# Main.net
KiCad netlist of a schematic drawn in Altium Designer
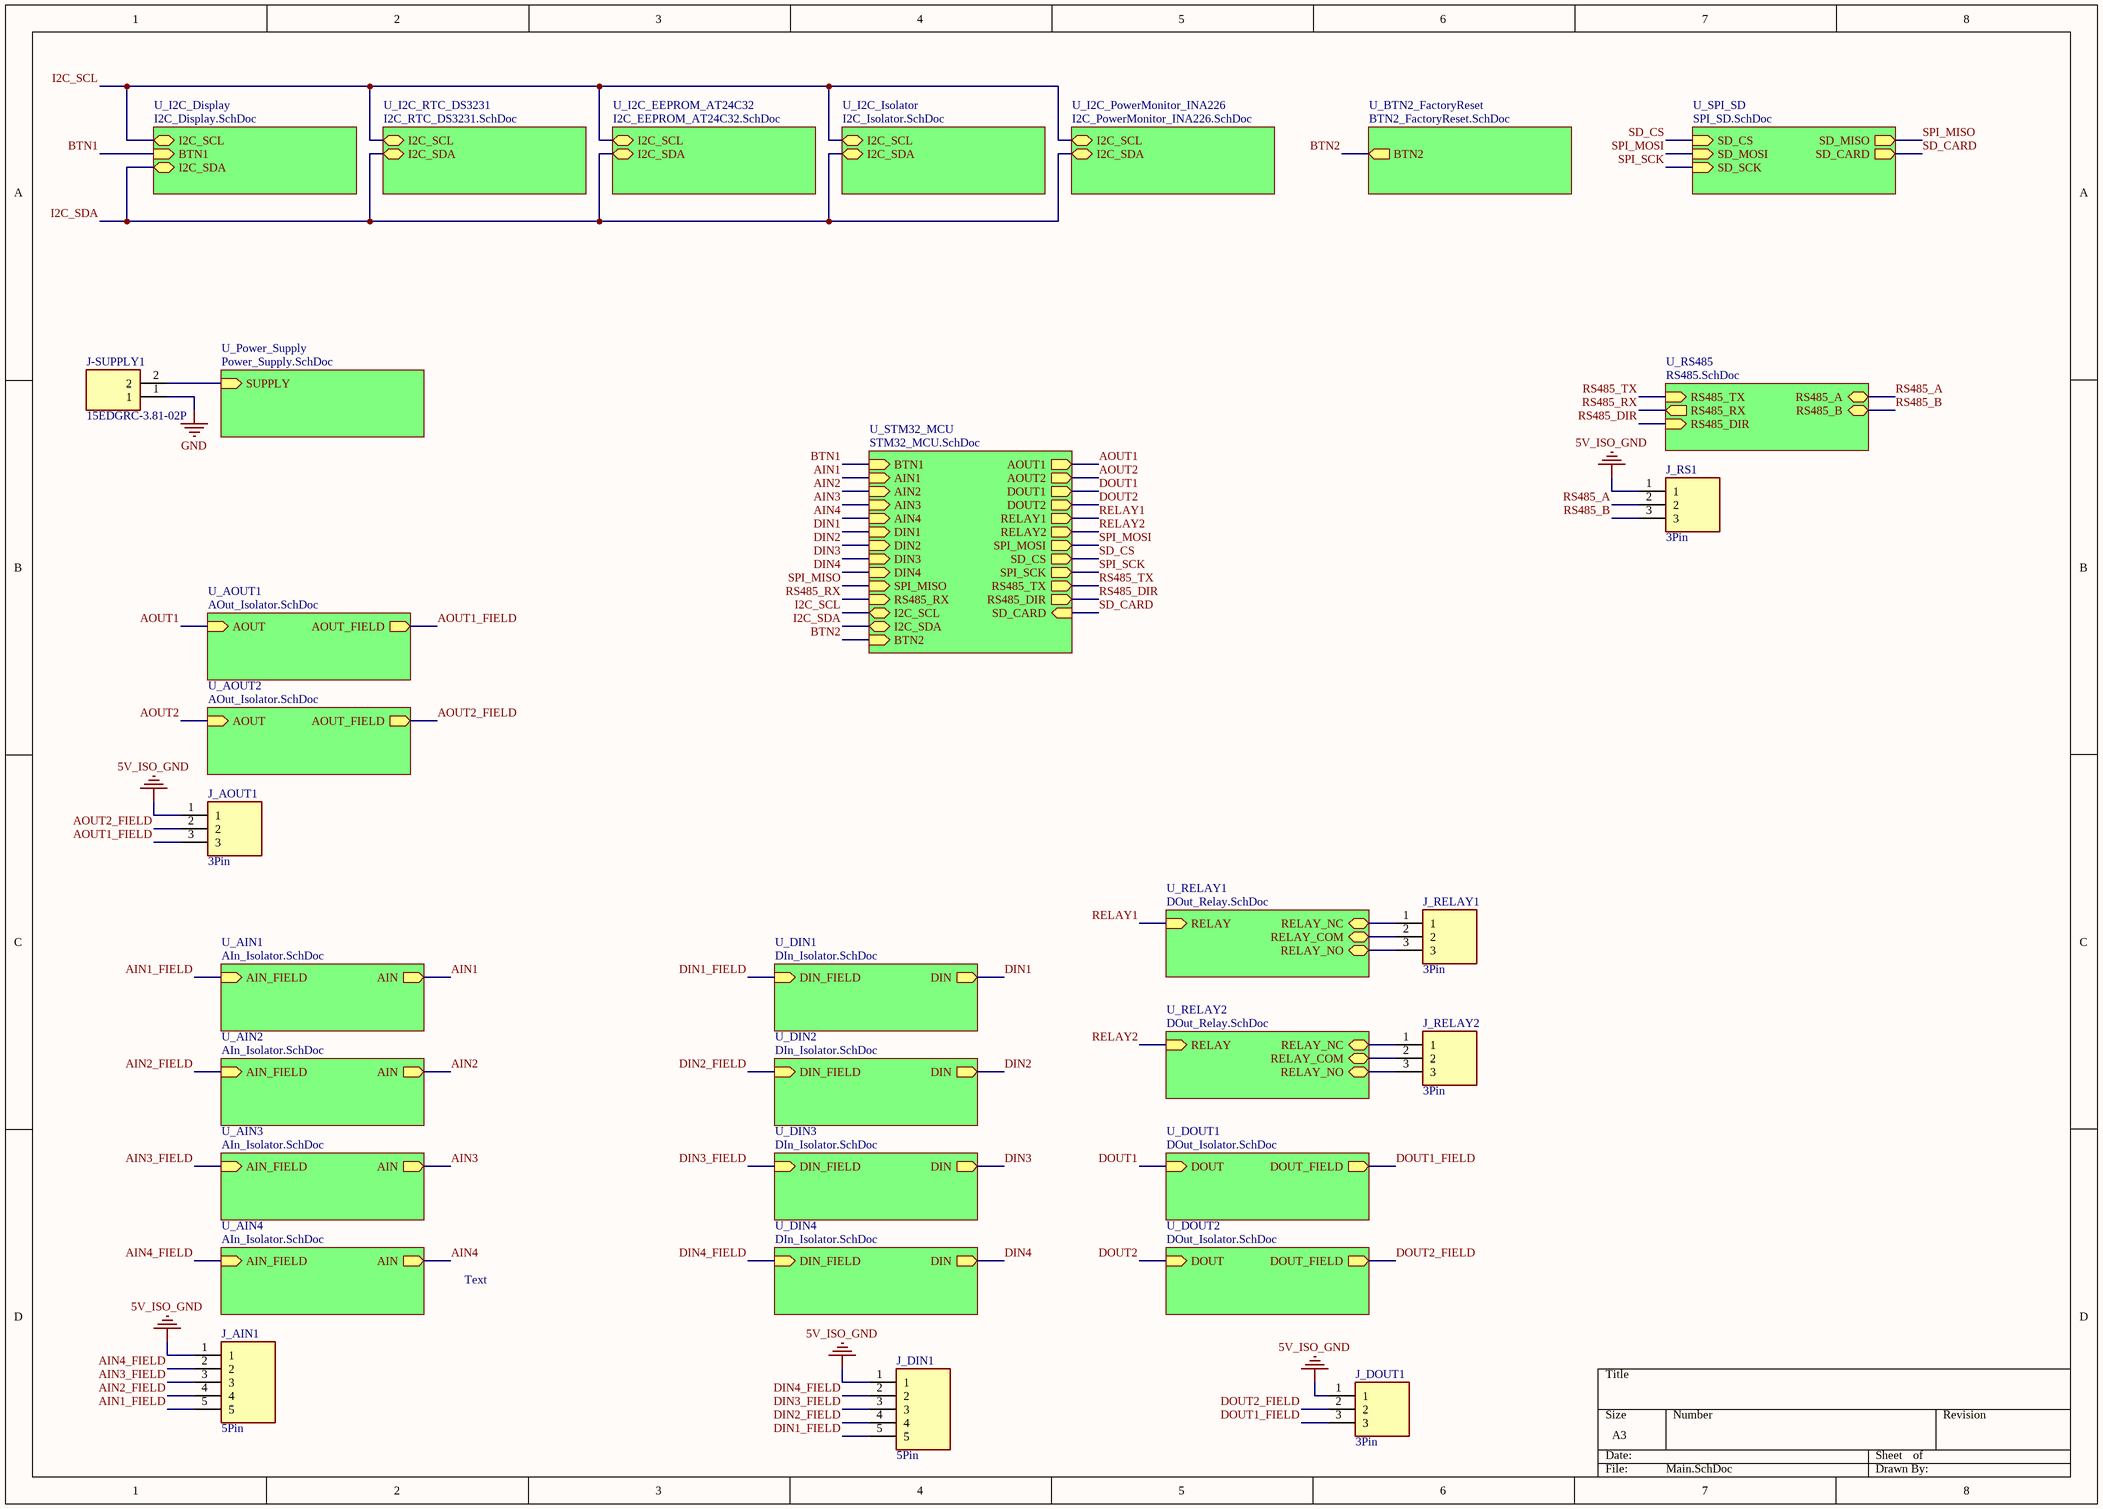
[diagram p0: Main.SchDoc]

(export (version "E")
  (design (tool "Eeschema 10.0.6"))
  (components
    (comp (ref "J-SUPPLY1")
      (value "15EDGRC-3.81-02P")
      (footprint "15EDGRC-3.81-02P")
      (fields (field (name "MANUFACTURER_PART_NUMBER") "15EDGRC-3.81-02P-14-00A(H)"))
      (libsource (lib "15EDGRC-3.81-02P") (part "15EDGRC-3.81-02P"))
    )
    (comp (ref "J_AIN1")
      (value "5Pin")
      (footprint "15EDGRC-3.81-05P:15EDGRC-3.81-05P")
      (fields (field (name "MANUFACTURER_PART_NUMBER") "15EDGRC-3.81-02P-14-00A(H)"))
      (libsource (lib "15EDGRC-3.81-05P") (part "15EDGRC-3.81-05P"))
    )
    (comp (ref "J_AOUT1")
      (value "3Pin")
      (footprint "15EDGRC-3.81-03P")
      (fields (field (name "MANUFACTURER_PART_NUMBER") "15EDGRC-3.81-02P-14-00A(H)"))
      (libsource (lib "15EDGRC-3.81-03P") (part "15EDGRC-3.81-03P"))
    )
    (comp (ref "J_DIN1")
      (value "5Pin")
      (footprint "15EDGRC-3.81-05P:15EDGRC-3.81-05P")
      (fields (field (name "MANUFACTURER_PART_NUMBER") "15EDGRC-3.81-02P-14-00A(H)"))
      (libsource (lib "15EDGRC-3.81-05P") (part "15EDGRC-3.81-05P"))
    )
    (comp (ref "J_DOUT1")
      (value "3Pin")
      (footprint "15EDGRC-3.81-03P")
      (fields (field (name "MANUFACTURER_PART_NUMBER") "15EDGRC-3.81-02P-14-00A(H)"))
      (libsource (lib "15EDGRC-3.81-03P") (part "15EDGRC-3.81-03P"))
    )
    (comp (ref "J_RELAY1")
      (value "3Pin")
      (footprint "15EDGRC-3.81-03P")
      (fields (field (name "MANUFACTURER_PART_NUMBER") "15EDGRC-3.81-02P-14-00A(H)"))
      (libsource (lib "15EDGRC-3.81-03P") (part "15EDGRC-3.81-03P"))
    )
    (comp (ref "J_RELAY2")
      (value "3Pin")
      (footprint "15EDGRC-3.81-03P")
      (fields (field (name "MANUFACTURER_PART_NUMBER") "15EDGRC-3.81-02P-14-00A(H)"))
      (libsource (lib "15EDGRC-3.81-03P") (part "15EDGRC-3.81-03P"))
    )
    (comp (ref "J_RS1")
      (value "3Pin")
      (footprint "15EDGRC-3.81-03P")
      (fields (field (name "MANUFACTURER_PART_NUMBER") "15EDGRC-3.81-02P-14-00A(H)"))
      (libsource (lib "15EDGRC-3.81-03P") (part "15EDGRC-3.81-03P"))
    )
  )
  (nets
    (net (code "2") (name "/AIN1_FIELD") (class "Default")
      (node (ref "J_AIN1") (pin "5") (pinfunction "5_5") (pintype "passive"))
    )
    (net (code "4") (name "/AIN2_FIELD") (class "Default")
      (node (ref "J_AIN1") (pin "4") (pinfunction "4_4") (pintype "passive"))
    )
    (net (code "6") (name "/AIN3_FIELD") (class "Default")
      (node (ref "J_AIN1") (pin "3") (pinfunction "3_3") (pintype "passive"))
    )
    (net (code "8") (name "/AIN4_FIELD") (class "Default")
      (node (ref "J_AIN1") (pin "2") (pinfunction "2_2") (pintype "passive"))
    )
    (net (code "10") (name "/AOUT1_FIELD") (class "Default")
      (node (ref "J_AOUT1") (pin "3") (pinfunction "3_3") (pintype "passive"))
    )
    (net (code "12") (name "/AOUT2_FIELD") (class "Default")
      (node (ref "J_AOUT1") (pin "2") (pinfunction "2_2") (pintype "passive"))
    )
    (net (code "16") (name "/DIN1_FIELD") (class "Default")
      (node (ref "J_DIN1") (pin "5") (pinfunction "5_5") (pintype "passive"))
    )
    (net (code "18") (name "/DIN2_FIELD") (class "Default")
      (node (ref "J_DIN1") (pin "4") (pinfunction "4_4") (pintype "passive"))
    )
    (net (code "20") (name "/DIN3_FIELD") (class "Default")
      (node (ref "J_DIN1") (pin "3") (pinfunction "3_3") (pintype "passive"))
    )
    (net (code "22") (name "/DIN4_FIELD") (class "Default")
      (node (ref "J_DIN1") (pin "2") (pinfunction "2_2") (pintype "passive"))
    )
    (net (code "24") (name "/DOUT1_FIELD") (class "Default")
      (node (ref "J_DOUT1") (pin "3") (pinfunction "3_3") (pintype "passive"))
    )
    (net (code "26") (name "/DOUT2_FIELD") (class "Default")
      (node (ref "J_DOUT1") (pin "2") (pinfunction "2_2") (pintype "passive"))
    )
    (net (code "31") (name "/RELAY_COM") (class "Default")
      (node (ref "J_RELAY2") (pin "2") (pinfunction "2_2") (pintype "passive"))
    )
    (net (code "32") (name "/RELAY_COM_1") (class "Default")
      (node (ref "J_RELAY1") (pin "2") (pinfunction "2_2") (pintype "passive"))
    )
    (net (code "33") (name "/RELAY_NC") (class "Default")
      (node (ref "J_RELAY2") (pin "1") (pinfunction "1_1") (pintype "passive"))
    )
    (net (code "34") (name "/RELAY_NC_1") (class "Default")
      (node (ref "J_RELAY1") (pin "1") (pinfunction "1_1") (pintype "passive"))
    )
    (net (code "35") (name "/RELAY_NO") (class "Default")
      (node (ref "J_RELAY2") (pin "3") (pinfunction "3_3") (pintype "passive"))
    )
    (net (code "36") (name "/RELAY_NO_1") (class "Default")
      (node (ref "J_RELAY1") (pin "3") (pinfunction "3_3") (pintype "passive"))
    )
    (net (code "37") (name "/RS485_A") (class "Default")
      (node (ref "J_RS1") (pin "2") (pinfunction "2_2") (pintype "passive"))
    )
    (net (code "38") (name "/RS485_B") (class "Default")
      (node (ref "J_RS1") (pin "3") (pinfunction "3_3") (pintype "passive"))
    )
    (net (code "47") (name "/SUPPLY") (class "Default")
      (node (ref "J-SUPPLY1") (pin "2") (pinfunction "2_2") (pintype "passive"))
    )
    (net (code "48") (name "5V_ISO_GND") (class "Default")
      (node (ref "J_AIN1") (pin "1") (pinfunction "1_1") (pintype "passive"))
      (node (ref "J_AOUT1") (pin "1") (pinfunction "1_1") (pintype "passive"))
      (node (ref "J_DIN1") (pin "1") (pinfunction "1_1") (pintype "passive"))
      (node (ref "J_DOUT1") (pin "1") (pinfunction "1_1") (pintype "passive"))
      (node (ref "J_RS1") (pin "1") (pinfunction "1_1") (pintype "passive"))
    )
    (net (code "49") (name "GND") (class "Default")
      (node (ref "J-SUPPLY1") (pin "1") (pinfunction "1_1") (pintype "passive"))
    )
  )
)
